# USB.net
KiCad netlist of a schematic drawn in Altium Designer
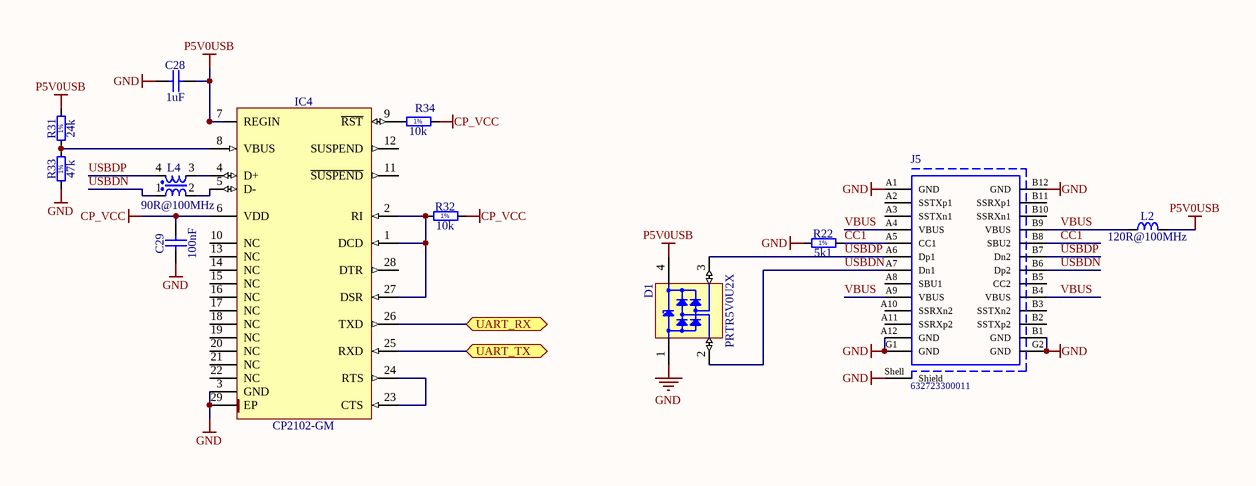
[diagram p0: USB.SchDoc]

(export (version "E")
  (design (tool "Eeschema 10.0.6"))
  (components
    (comp (ref "C28")
      (value "1uF")
      (footprint "CAPC1005X55N")
      (description "Non-polarised capacitor")
      (fields
        (field (name "PART NUMBER") "CC0402_1UF_16V_10%_X5R")
        (field (name "VOLTAGE") "16V")
        (field (name "AUTHOR") "CERN DEM JLC")
      )
      (libsource (lib "Capacitors") (part "Capacitor - non polarized"))
    )
    (comp (ref "C29")
      (value "100nF")
      (footprint "CAPC1608X87N")
      (description "Non-polarised capacitor")
      (fields
        (field (name "PART NUMBER") "CC0603_100NF_50V_10%_X5R")
        (field (name "VOLTAGE") "50V")
        (field (name "AUTHOR") "CERN DEM MR")
      )
      (libsource (lib "Capacitors") (part "Capacitor - non polarized"))
    )
    (comp (ref "D1")
      (value "PRTR5V0U2X")
      (footprint "SOT190P230X110-4N")
      (description "Ultra Low Capacitance Double Rail-to-Rail ESD Protection Diode")
      (fields
        (field (name "VOLTAGE") "5.5V")
        (field (name "MANUFACTURER") "NXP SEMICONDUCTORS")
        (field (name "AUTHOR") "CERN DEM JLC")
      )
      (libsource (lib "ICs And Semiconductors") (part "PRTR5V0U2X"))
    )
    (comp (ref "IC4")
      (value "CP2102-GM")
      (footprint "QFN50P500X500X100-29N-S335")
      (description "Single-Chip USB to UART Bridge")
      (fields (field (name "MANUFACTURER") "SILICON LABS") (field (name "AUTHOR") "CERN DEM JLC"))
      (libsource (lib "ICs And Semiconductors") (part "CP2102-GM"))
    )
    (comp (ref "J5")
      (value "632723300011")
      (footprint "632723300011")
      (description "USB 3.1 Type C Receptacle WR-COM, Horizontal, SMT / THT")
      (fields (field (name "MANUFACTURER") "Wurth Elektronik"))
      (libsource (lib "ALTIUM-WR-COM_USB_31-rev19a") (part "632723300011"))
    )
    (comp (ref "L2")
      (value "120R@100MHz")
      (footprint "INDC1608X65N")
      (description "Ferrite Bead")
      (fields
        (field (name "PART NUMBER") "BLM18SG121TN1D")
        (field (name "POWER") "3A")
        (field (name "AUTHOR") "CERN DEM JLC")
      )
      (libsource (lib "Inductors & Transformers") (part "Inductor"))
    )
    (comp (ref "L4")
      (value "90R@100MHz")
      (footprint "IND_MURATA_DLW21S")
      (description "Inductor Common Mode")
      (fields
        (field (name "PART NUMBER") "DLW21SN900SQ2L")
        (field (name "POWER") "330mA")
        (field (name "AUTHOR") "CERN DEM JLC")
      )
      (libsource (lib "Inductors & Transformers") (part "Inductor Common Mode 1Dot-2 4Dot-3"))
    )
    (comp (ref "R22")
      (value "5k1")
      (footprint "RESC1005X40N")
      (description "Resistor - 1%")
      (fields
        (field (name "PART NUMBER") "R0402_5K1_1%_0.0625W_100PPM")
        (field (name "POWER") "0.0625W")
        (field (name "AUTHOR") "CERN DEM JLC")
      )
      (libsource (lib "Resistors") (part "Resistor - 1%"))
    )
    (comp (ref "R31")
      (value "24k")
      (footprint "RESC1005X40N")
      (description "Resistor - 1%")
      (fields
        (field (name "PART NUMBER") "R0402_24K_1%_0.0625W_100PPM")
        (field (name "POWER") "0.0625W")
        (field (name "AUTHOR") "CERN DEM JLC")
      )
      (libsource (lib "Resistors") (part "Resistor - 1%"))
    )
    (comp (ref "R32")
      (value "10k")
      (footprint "RESC1608X55N")
      (description "Resistor - 1%")
      (fields
        (field (name "PART NUMBER") "R0603_10K_1%_0.1W_100PPM")
        (field (name "POWER") "0.1W")
        (field (name "AUTHOR") "CERN DEM JLC")
      )
      (libsource (lib "Resistors") (part "Resistor - 1%"))
    )
    (comp (ref "R33")
      (value "47k")
      (footprint "RESC1005X40N")
      (description "Resistor - 1%")
      (fields
        (field (name "PART NUMBER") "R0402_47K_1%_0.0625W_100PPM")
        (field (name "POWER") "0.0625W")
        (field (name "AUTHOR") "CERN DEM JLC")
      )
      (libsource (lib "Resistors") (part "Resistor - 1%"))
    )
    (comp (ref "R34")
      (value "10k")
      (footprint "RESC1608X55N")
      (description "Resistor - 1%")
      (fields
        (field (name "PART NUMBER") "R0603_10K_1%_0.1W_100PPM")
        (field (name "POWER") "0.1W")
        (field (name "AUTHOR") "CERN DEM JLC")
      )
      (libsource (lib "Resistors") (part "Resistor - 1%"))
    )
  )
  (nets
    (net (code "1") (name "/CC1") (class "Default")
      (node (ref "J5") (pin "A5") (pinfunction "CC1_A5") (pintype "passive"))
      (node (ref "J5") (pin "B8") (pinfunction "SBU2_B8") (pintype "passive"))
      (node (ref "R22") (pin "2") (pinfunction "2_2") (pintype "passive"))
    )
    (net (code "2") (name "/UART_RX") (class "Default")
      (node (ref "IC4") (pin "26") (pinfunction "TXD_26") (pintype "output"))
    )
    (net (code "3") (name "/UART_TX") (class "Default")
      (node (ref "IC4") (pin "25") (pinfunction "RXD_25") (pintype "input"))
    )
    (net (code "4") (name "/USBDN") (class "Default")
      (node (ref "D1") (pin "2") (pinfunction "I/O1_2") (pintype "bidirectional"))
      (node (ref "J5") (pin "A7") (pinfunction "Dn1_A7") (pintype "passive"))
      (node (ref "J5") (pin "B6") (pinfunction "Dp2_B6") (pintype "passive"))
      (node (ref "L4") (pin "1") (pinfunction "1_1") (pintype "passive"))
    )
    (net (code "5") (name "/USBDP") (class "Default")
      (node (ref "D1") (pin "3") (pinfunction "I/O2_3") (pintype "bidirectional"))
      (node (ref "J5") (pin "A6") (pinfunction "Dp1_A6") (pintype "passive"))
      (node (ref "J5") (pin "B7") (pinfunction "Dn2_B7") (pintype "passive"))
      (node (ref "L4") (pin "4") (pinfunction "4_4") (pintype "passive"))
    )
    (net (code "6") (name "/VBUS") (class "Default")
      (node (ref "J5") (pin "A4") (pinfunction "VBUS_A4") (pintype "passive"))
      (node (ref "J5") (pin "A9") (pinfunction "VBUS_A9") (pintype "passive"))
      (node (ref "J5") (pin "B4") (pinfunction "VBUS_B4") (pintype "passive"))
      (node (ref "J5") (pin "B9") (pinfunction "VBUS_B9") (pintype "passive"))
      (node (ref "L2") (pin "1") (pinfunction "1_1") (pintype "passive"))
    )
    (net (code "7") (name "CP_VCC") (class "Default")
      (node (ref "C29") (pin "2") (pinfunction "2_2") (pintype "passive"))
      (node (ref "IC4") (pin "6") (pinfunction "VDD_6") (pintype "power_in"))
      (node (ref "R32") (pin "2") (pinfunction "2_2") (pintype "passive"))
      (node (ref "R34") (pin "2") (pinfunction "2_2") (pintype "passive"))
    )
    (net (code "8") (name "GND") (class "Default")
      (node (ref "C28") (pin "1") (pinfunction "1_1") (pintype "passive"))
      (node (ref "C29") (pin "1") (pinfunction "1_1") (pintype "passive"))
      (node (ref "D1") (pin "1") (pinfunction "GND_1") (pintype "power_in"))
      (node (ref "IC4") (pin "29") (pinfunction "EP_29") (pintype "power_in"))
      (node (ref "IC4") (pin "3") (pinfunction "GND_3") (pintype "power_in"))
      (node (ref "J5") (pin "A1") (pinfunction "GND_A1") (pintype "passive"))
      (node (ref "J5") (pin "A12") (pinfunction "GND_A12") (pintype "passive"))
      (node (ref "J5") (pin "B1") (pinfunction "GND_B1") (pintype "passive"))
      (node (ref "J5") (pin "B12") (pinfunction "GND_B12") (pintype "passive"))
      (node (ref "J5") (pin "G1") (pinfunction "GND_G1") (pintype "passive"))
      (node (ref "J5") (pin "G2") (pinfunction "GND_G2") (pintype "passive"))
      (node (ref "J5") (pin "Shell") (pinfunction "Shield_Shell") (pintype "passive"))
      (node (ref "R22") (pin "1") (pinfunction "1_1") (pintype "passive"))
      (node (ref "R33") (pin "1") (pinfunction "1_1") (pintype "passive"))
    )
    (net (code "9") (name "Net-(IC4-CTS)") (class "Default")
      (node (ref "IC4") (pin "23") (pinfunction "CTS_23") (pintype "input"))
      (node (ref "IC4") (pin "24") (pinfunction "RTS_24") (pintype "output"))
    )
    (net (code "10") (name "Net-(IC4-D+)") (class "Default")
      (node (ref "IC4") (pin "4") (pinfunction "D+_4") (pintype "bidirectional"))
      (node (ref "L4") (pin "3") (pinfunction "3_3") (pintype "passive"))
    )
    (net (code "11") (name "Net-(IC4-D-)") (class "Default")
      (node (ref "IC4") (pin "5") (pinfunction "D-_5") (pintype "bidirectional"))
      (node (ref "L4") (pin "2") (pinfunction "2_2") (pintype "passive"))
    )
    (net (code "12") (name "Net-(IC4-DCD)") (class "Default")
      (node (ref "IC4") (pin "1") (pinfunction "DCD_1") (pintype "input"))
      (node (ref "IC4") (pin "2") (pinfunction "RI_2") (pintype "input"))
      (node (ref "IC4") (pin "27") (pinfunction "DSR_27") (pintype "input"))
      (node (ref "R32") (pin "1") (pinfunction "1_1") (pintype "passive"))
    )
    (net (code "13") (name "Net-(IC4-VBUS)") (class "Default")
      (node (ref "IC4") (pin "8") (pinfunction "VBUS_8") (pintype "input"))
      (node (ref "R31") (pin "1") (pinfunction "1_1") (pintype "passive"))
      (node (ref "R33") (pin "2") (pinfunction "2_2") (pintype "passive"))
    )
    (net (code "14") (name "Net-(IC4-~{RST})") (class "Default")
      (node (ref "IC4") (pin "9") (pinfunction "~{RST}_9") (pintype "bidirectional"))
      (node (ref "R34") (pin "1") (pinfunction "1_1") (pintype "passive"))
    )
    (net (code "15") (name "P5V0USB") (class "Default")
      (node (ref "C28") (pin "2") (pinfunction "2_2") (pintype "passive"))
      (node (ref "D1") (pin "4") (pinfunction "VCC_4") (pintype "power_in"))
      (node (ref "IC4") (pin "7") (pinfunction "REGIN_7") (pintype "power_in"))
      (node (ref "L2") (pin "2") (pinfunction "2_2") (pintype "passive"))
      (node (ref "R31") (pin "2") (pinfunction "2_2") (pintype "passive"))
    )
    (net (code "16") (name "unconnected-(IC4-DTR-Pad28)") (class "Default")
      (node (ref "IC4") (pin "28") (pinfunction "DTR_28") (pintype "output"))
    )
    (net (code "17") (name "unconnected-(IC4-NC-Pad10)") (class "Default")
      (node (ref "IC4") (pin "10") (pinfunction "NC_10") (pintype "passive"))
    )
    (net (code "18") (name "unconnected-(IC4-NC-Pad13)") (class "Default")
      (node (ref "IC4") (pin "13") (pinfunction "NC_13") (pintype "passive"))
    )
    (net (code "19") (name "unconnected-(IC4-NC-Pad14)") (class "Default")
      (node (ref "IC4") (pin "14") (pinfunction "NC_14") (pintype "passive"))
    )
    (net (code "20") (name "unconnected-(IC4-NC-Pad15)") (class "Default")
      (node (ref "IC4") (pin "15") (pinfunction "NC_15") (pintype "passive"))
    )
    (net (code "21") (name "unconnected-(IC4-NC-Pad16)") (class "Default")
      (node (ref "IC4") (pin "16") (pinfunction "NC_16") (pintype "passive"))
    )
    (net (code "22") (name "unconnected-(IC4-NC-Pad17)") (class "Default")
      (node (ref "IC4") (pin "17") (pinfunction "NC_17") (pintype "passive"))
    )
    (net (code "23") (name "unconnected-(IC4-NC-Pad18)") (class "Default")
      (node (ref "IC4") (pin "18") (pinfunction "NC_18") (pintype "passive"))
    )
    (net (code "24") (name "unconnected-(IC4-NC-Pad19)") (class "Default")
      (node (ref "IC4") (pin "19") (pinfunction "NC_19") (pintype "passive"))
    )
    (net (code "25") (name "unconnected-(IC4-NC-Pad20)") (class "Default")
      (node (ref "IC4") (pin "20") (pinfunction "NC_20") (pintype "passive"))
    )
    (net (code "26") (name "unconnected-(IC4-NC-Pad21)") (class "Default")
      (node (ref "IC4") (pin "21") (pinfunction "NC_21") (pintype "passive"))
    )
    (net (code "27") (name "unconnected-(IC4-NC-Pad22)") (class "Default")
      (node (ref "IC4") (pin "22") (pinfunction "NC_22") (pintype "passive"))
    )
    (net (code "28") (name "unconnected-(IC4-SUSPEND-Pad12)") (class "Default")
      (node (ref "IC4") (pin "12") (pinfunction "SUSPEND_12") (pintype "output"))
    )
    (net (code "29") (name "unconnected-(IC4-~{SUSPEND}-Pad11)") (class "Default")
      (node (ref "IC4") (pin "11") (pinfunction "~{SUSPEND}_11") (pintype "output"))
    )
    (net (code "30") (name "unconnected-(J5-CC2-PadB5)") (class "Default")
      (node (ref "J5") (pin "B5") (pinfunction "CC2_B5") (pintype "passive"))
    )
    (net (code "31") (name "unconnected-(J5-SBU1-PadA8)") (class "Default")
      (node (ref "J5") (pin "A8") (pinfunction "SBU1_A8") (pintype "passive"))
    )
    (net (code "32") (name "unconnected-(J5-SSRXn1-PadB10)") (class "Default")
      (node (ref "J5") (pin "B10") (pinfunction "SSRXn1_B10") (pintype "passive"))
    )
    (net (code "33") (name "unconnected-(J5-SSRXn2-PadA10)") (class "Default")
      (node (ref "J5") (pin "A10") (pinfunction "SSRXn2_A10") (pintype "passive"))
    )
    (net (code "34") (name "unconnected-(J5-SSRXp1-PadB11)") (class "Default")
      (node (ref "J5") (pin "B11") (pinfunction "SSRXp1_B11") (pintype "passive"))
    )
    (net (code "35") (name "unconnected-(J5-SSRXp2-PadA11)") (class "Default")
      (node (ref "J5") (pin "A11") (pinfunction "SSRXp2_A11") (pintype "passive"))
    )
    (net (code "36") (name "unconnected-(J5-SSTXn1-PadA3)") (class "Default")
      (node (ref "J5") (pin "A3") (pinfunction "SSTXn1_A3") (pintype "passive"))
    )
    (net (code "37") (name "unconnected-(J5-SSTXn2-PadB3)") (class "Default")
      (node (ref "J5") (pin "B3") (pinfunction "SSTXn2_B3") (pintype "passive"))
    )
    (net (code "38") (name "unconnected-(J5-SSTXp1-PadA2)") (class "Default")
      (node (ref "J5") (pin "A2") (pinfunction "SSTXp1_A2") (pintype "passive"))
    )
    (net (code "39") (name "unconnected-(J5-SSTXp2-PadB2)") (class "Default")
      (node (ref "J5") (pin "B2") (pinfunction "SSTXp2_B2") (pintype "passive"))
    )
  )
)
